# Rear_brake_lamp_v3B.net
KiCad netlist of a schematic drawn in EAGLE
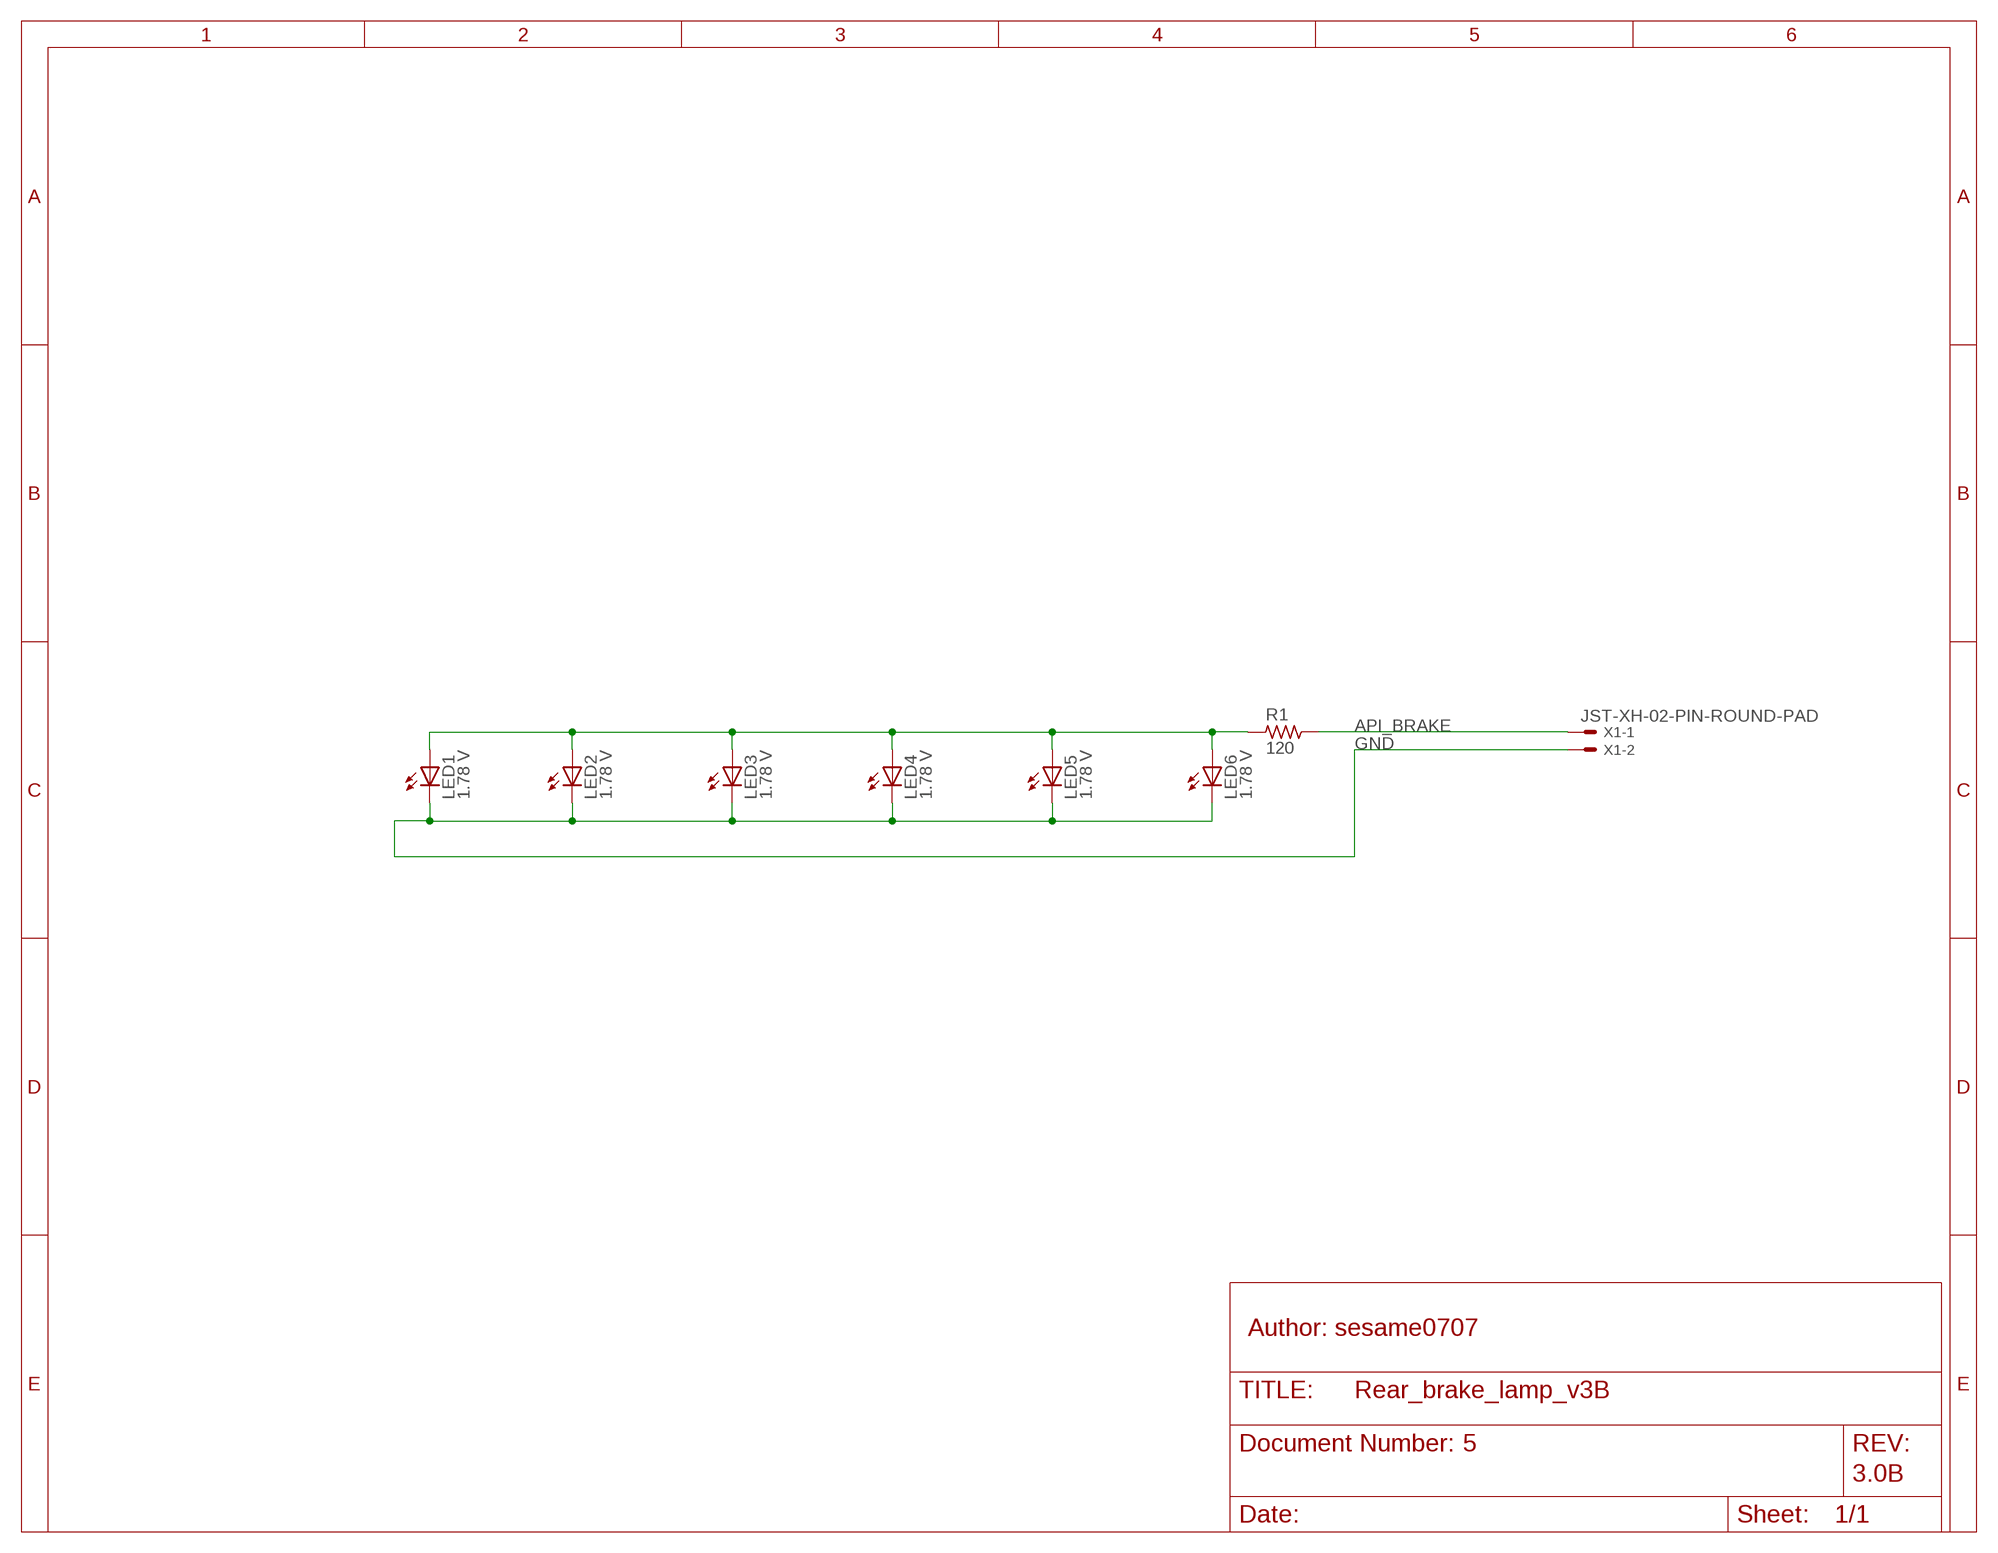
[diagram p0: schematic, sheet 1]

(export (version "E")
  (design (tool "Eeschema 10.0.6"))
  (components
    (comp (ref "LED1")
      (value "1.78 V")
      (footprint "eagle-import:LED5MM")
      (libsource (lib "eagle-import") (part "LED5MM"))
    )
    (comp (ref "LED2")
      (value "1.78 V")
      (footprint "eagle-import:LED5MM")
      (libsource (lib "eagle-import") (part "LED5MM"))
    )
    (comp (ref "LED3")
      (value "1.78 V")
      (footprint "eagle-import:LED5MM")
      (libsource (lib "eagle-import") (part "LED5MM"))
    )
    (comp (ref "LED4")
      (value "1.78 V")
      (footprint "eagle-import:LED5MM")
      (libsource (lib "eagle-import") (part "LED5MM"))
    )
    (comp (ref "LED5")
      (value "1.78 V")
      (footprint "eagle-import:LED5MM")
      (libsource (lib "eagle-import") (part "LED5MM"))
    )
    (comp (ref "LED6")
      (value "1.78 V")
      (footprint "eagle-import:LED5MM")
      (libsource (lib "eagle-import") (part "LED5MM"))
    )
    (comp (ref "R1")
      (value "120")
      (footprint "eagle-import:R1206")
      (libsource (lib "eagle-import") (part "R_1206"))
    )
    (comp (ref "X1")
      (value "JST-XH-02-PIN-ROUND-PAD")
      (footprint "eagle-import:JST-XH-02-PACKAGE-ROUND-PAD")
      (libsource (lib "eagle-import") (part "JST-XH-02-PIN-ROUND-PAD"))
    )
  )
  (nets
    (net (code "1") (name "/API_BRAKE") (class "Default")
      (node (ref "LED1") (pin "A") (pinfunction "A_A") (pintype "passive"))
      (node (ref "LED2") (pin "A") (pinfunction "A_A") (pintype "passive"))
      (node (ref "LED3") (pin "A") (pinfunction "A_A") (pintype "passive"))
      (node (ref "LED4") (pin "A") (pinfunction "A_A") (pintype "passive"))
      (node (ref "LED5") (pin "A") (pinfunction "A_A") (pintype "passive"))
      (node (ref "LED6") (pin "A") (pinfunction "A_A") (pintype "passive"))
      (node (ref "R1") (pin "1") (pinfunction "1_1") (pintype "passive"))
    )
    (net (code "2") (name "/GND") (class "Default")
      (node (ref "LED1") (pin "K") (pinfunction "C_K") (pintype "passive"))
      (node (ref "LED2") (pin "K") (pinfunction "C_K") (pintype "passive"))
      (node (ref "LED3") (pin "K") (pinfunction "C_K") (pintype "passive"))
      (node (ref "LED4") (pin "K") (pinfunction "C_K") (pintype "passive"))
      (node (ref "LED5") (pin "K") (pinfunction "C_K") (pintype "passive"))
      (node (ref "LED6") (pin "K") (pinfunction "C_K") (pintype "passive"))
      (node (ref "X1") (pin "2") (pinfunction "S_2") (pintype "passive"))
    )
    (net (code "3") (name "Net-(X1A-S)") (class "Default")
      (node (ref "R1") (pin "2") (pinfunction "2_2") (pintype "passive"))
      (node (ref "X1") (pin "1") (pinfunction "S_1") (pintype "passive"))
    )
  )
)
